# RPi-Proto-HAT_v10.net
KiCad netlist of a schematic drawn in EAGLE
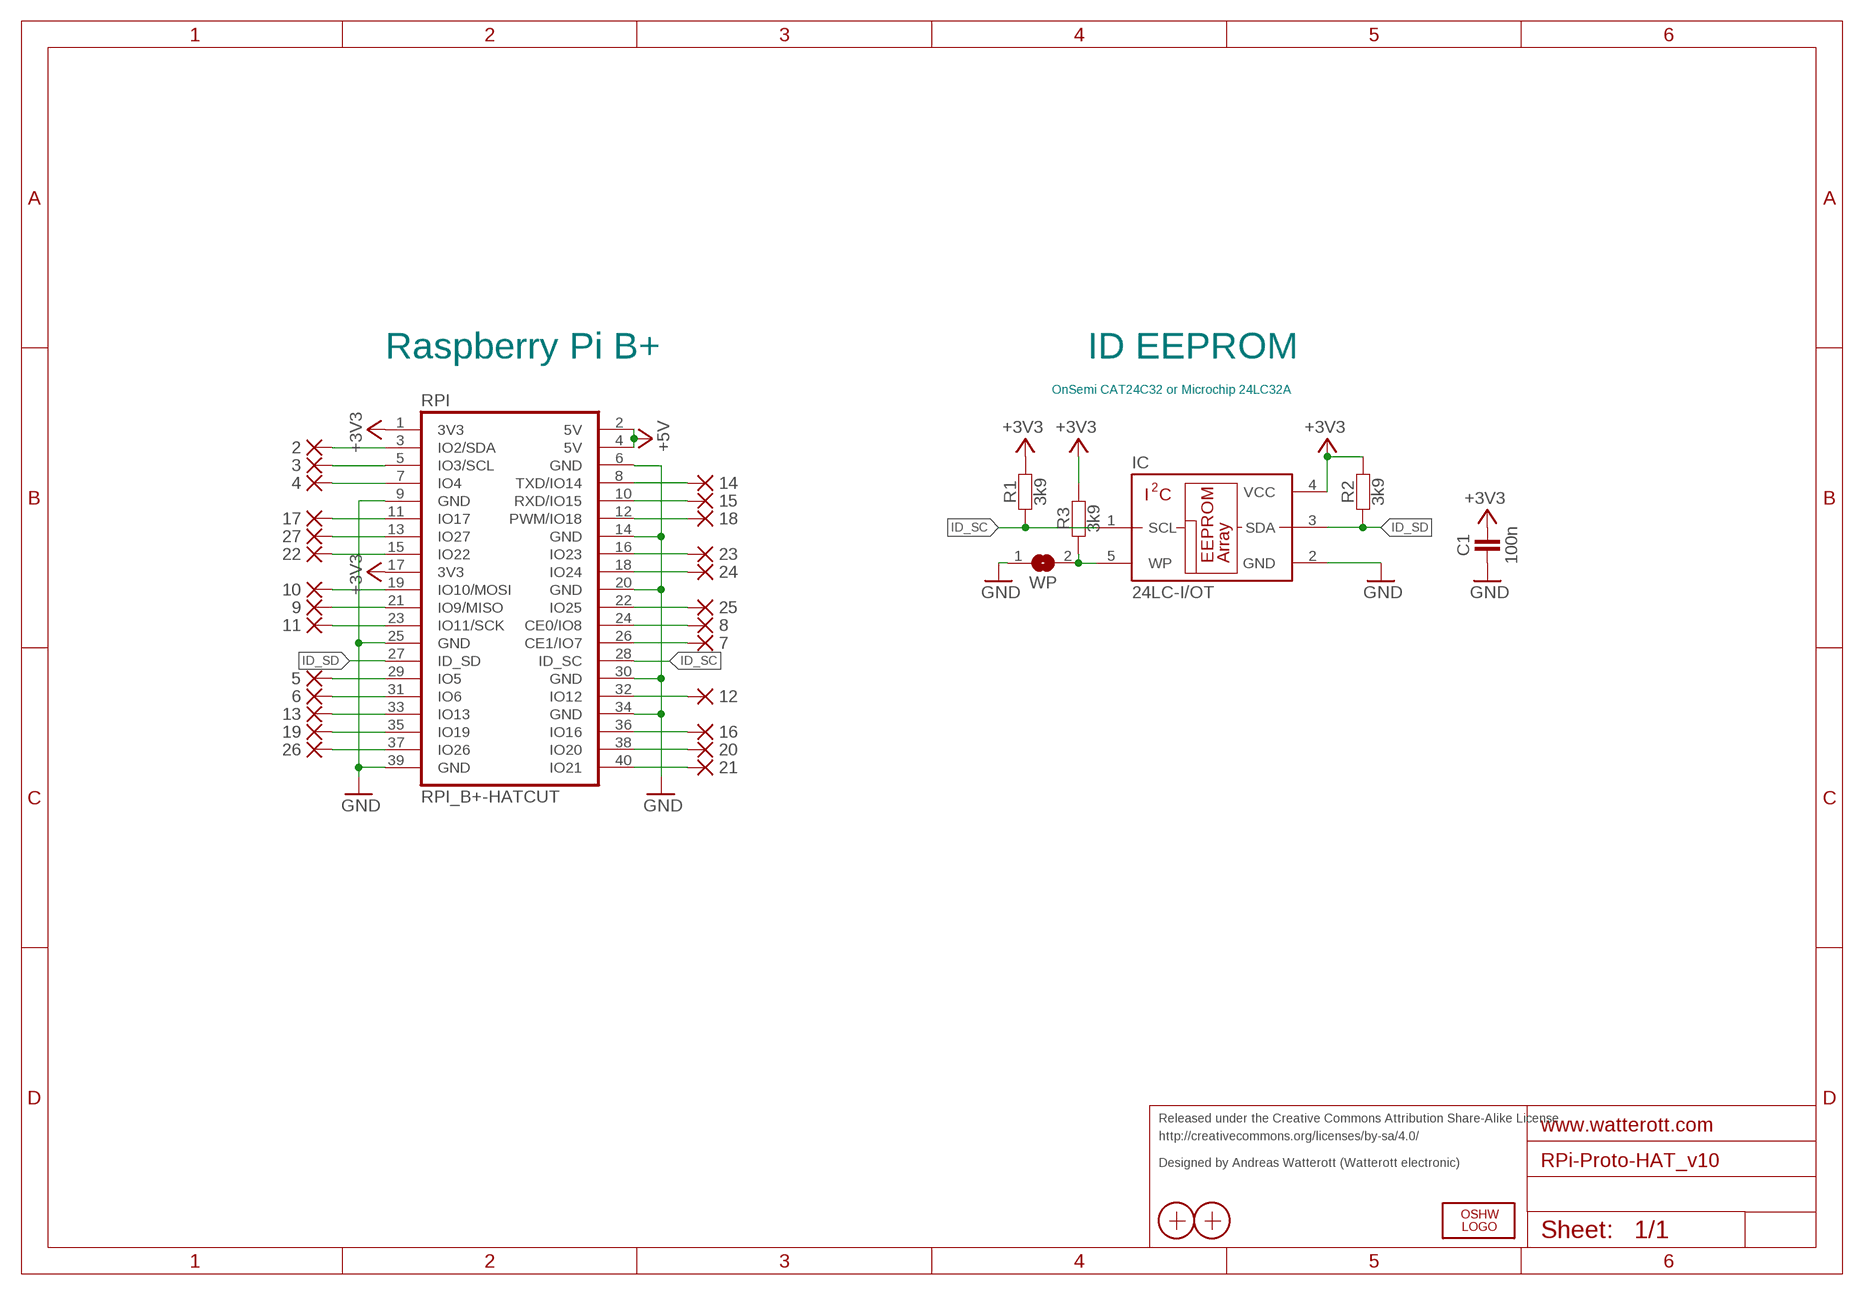
[diagram p0: schematic, sheet 1]

(export (version "E")
  (design (tool "Eeschema 10.0.6"))
  (components
    (comp (ref "2")
      (value "PAD-1-1.6")
      (footprint "eagle-import:PAD-1-1.6")
      (libsource (lib "eagle-import") (part "PAD-1-1.6"))
    )
    (comp (ref "3")
      (value "PAD-1-1.6")
      (footprint "eagle-import:PAD-1-1.6")
      (libsource (lib "eagle-import") (part "PAD-1-1.6"))
    )
    (comp (ref "4")
      (value "PAD-1-1.6")
      (footprint "eagle-import:PAD-1-1.6")
      (libsource (lib "eagle-import") (part "PAD-1-1.6"))
    )
    (comp (ref "5")
      (value "PAD-1-1.6")
      (footprint "eagle-import:PAD-1-1.6")
      (libsource (lib "eagle-import") (part "PAD-1-1.6"))
    )
    (comp (ref "6")
      (value "PAD-1-1.6")
      (footprint "eagle-import:PAD-1-1.6")
      (libsource (lib "eagle-import") (part "PAD-1-1.6"))
    )
    (comp (ref "7")
      (value "PAD-1-1.6")
      (footprint "eagle-import:PAD-1-1.6")
      (libsource (lib "eagle-import") (part "PAD-1-1.6"))
    )
    (comp (ref "8")
      (value "PAD-1-1.6")
      (footprint "eagle-import:PAD-1-1.6")
      (libsource (lib "eagle-import") (part "PAD-1-1.6"))
    )
    (comp (ref "9")
      (value "PAD-1-1.6")
      (footprint "eagle-import:PAD-1-1.6")
      (libsource (lib "eagle-import") (part "PAD-1-1.6"))
    )
    (comp (ref "10")
      (value "PAD-1-1.6")
      (footprint "eagle-import:PAD-1-1.6")
      (libsource (lib "eagle-import") (part "PAD-1-1.6"))
    )
    (comp (ref "11")
      (value "PAD-1-1.6")
      (footprint "eagle-import:PAD-1-1.6")
      (libsource (lib "eagle-import") (part "PAD-1-1.6"))
    )
    (comp (ref "12")
      (value "PAD-1-1.6")
      (footprint "eagle-import:PAD-1-1.6")
      (libsource (lib "eagle-import") (part "PAD-1-1.6"))
    )
    (comp (ref "13")
      (value "PAD-1-1.6")
      (footprint "eagle-import:PAD-1-1.6")
      (libsource (lib "eagle-import") (part "PAD-1-1.6"))
    )
    (comp (ref "14")
      (value "PAD-1-1.6")
      (footprint "eagle-import:PAD-1-1.6")
      (libsource (lib "eagle-import") (part "PAD-1-1.6"))
    )
    (comp (ref "15")
      (value "PAD-1-1.6")
      (footprint "eagle-import:PAD-1-1.6")
      (libsource (lib "eagle-import") (part "PAD-1-1.6"))
    )
    (comp (ref "16")
      (value "PAD-1-1.6")
      (footprint "eagle-import:PAD-1-1.6")
      (libsource (lib "eagle-import") (part "PAD-1-1.6"))
    )
    (comp (ref "17")
      (value "PAD-1-1.6")
      (footprint "eagle-import:PAD-1-1.6")
      (libsource (lib "eagle-import") (part "PAD-1-1.6"))
    )
    (comp (ref "18")
      (value "PAD-1-1.6")
      (footprint "eagle-import:PAD-1-1.6")
      (libsource (lib "eagle-import") (part "PAD-1-1.6"))
    )
    (comp (ref "19")
      (value "PAD-1-1.6")
      (footprint "eagle-import:PAD-1-1.6")
      (libsource (lib "eagle-import") (part "PAD-1-1.6"))
    )
    (comp (ref "20")
      (value "PAD-1-1.6")
      (footprint "eagle-import:PAD-1-1.6")
      (libsource (lib "eagle-import") (part "PAD-1-1.6"))
    )
    (comp (ref "21")
      (value "PAD-1-1.6")
      (footprint "eagle-import:PAD-1-1.6")
      (libsource (lib "eagle-import") (part "PAD-1-1.6"))
    )
    (comp (ref "22")
      (value "PAD-1-1.6")
      (footprint "eagle-import:PAD-1-1.6")
      (libsource (lib "eagle-import") (part "PAD-1-1.6"))
    )
    (comp (ref "23")
      (value "PAD-1-1.6")
      (footprint "eagle-import:PAD-1-1.6")
      (libsource (lib "eagle-import") (part "PAD-1-1.6"))
    )
    (comp (ref "24")
      (value "PAD-1-1.6")
      (footprint "eagle-import:PAD-1-1.6")
      (libsource (lib "eagle-import") (part "PAD-1-1.6"))
    )
    (comp (ref "25")
      (value "PAD-1-1.6")
      (footprint "eagle-import:PAD-1-1.6")
      (libsource (lib "eagle-import") (part "PAD-1-1.6"))
    )
    (comp (ref "26")
      (value "PAD-1-1.6")
      (footprint "eagle-import:PAD-1-1.6")
      (libsource (lib "eagle-import") (part "PAD-1-1.6"))
    )
    (comp (ref "27")
      (value "PAD-1-1.6")
      (footprint "eagle-import:PAD-1-1.6")
      (libsource (lib "eagle-import") (part "PAD-1-1.6"))
    )
    (comp (ref "C1")
      (value "100n")
      (footprint "eagle-import:R0603")
      (libsource (lib "eagle-import") (part "CAPACITOR-C0603"))
    )
    (comp (ref "IC")
      (value "24LC-I/OT")
      (footprint "eagle-import:SOT23-5")
      (libsource (lib "eagle-import") (part "24LC-I/OT"))
    )
    (comp (ref "LOGO2")
      (value "OSHW_LOGOX0070")
      (footprint "eagle-import:OSHW_6X70")
      (libsource (lib "eagle-import") (part "OSHW_LOGOX0070"))
    )
    (comp (ref "R1")
      (value "3k9")
      (footprint "eagle-import:R0603")
      (libsource (lib "eagle-import") (part "RESISTOR-R0603"))
    )
    (comp (ref "R2")
      (value "3k9")
      (footprint "eagle-import:R0603")
      (libsource (lib "eagle-import") (part "RESISTOR-R0603"))
    )
    (comp (ref "R3")
      (value "3k9")
      (footprint "eagle-import:R0603")
      (libsource (lib "eagle-import") (part "RESISTOR-R0603"))
    )
    (comp (ref "RPI")
      (value "RPI_B+-HATCUT")
      (footprint "eagle-import:RPI-B+HAT_CUTOUT")
      (libsource (lib "eagle-import") (part "RPI_B+-HATCUT"))
    )
    (comp (ref "WP")
      (value "JUMPER2-NOCREAM")
      (footprint "eagle-import:JUMPER2_NC")
      (libsource (lib "eagle-import") (part "JUMPER2-NOCREAM"))
    )
    (comp (ref "X1")
      (value "PASSER-07")
      (footprint "eagle-import:PASSER_07MM")
      (libsource (lib "eagle-import") (part "PASSER-07"))
    )
    (comp (ref "X2")
      (value "PASSER-07")
      (footprint "eagle-import:PASSER_07MM")
      (libsource (lib "eagle-import") (part "PASSER-07"))
    )
  )
  (nets
    (net (code "1") (name "+3V3") (class "Default")
      (node (ref "C1") (pin "2") (pinfunction "2_2") (pintype "passive"))
      (node (ref "IC") (pin "4") (pinfunction "VCC_4") (pintype "power_in"))
      (node (ref "R1") (pin "2") (pinfunction "2_2") (pintype "passive"))
      (node (ref "R2") (pin "2") (pinfunction "2_2") (pintype "passive"))
      (node (ref "R3") (pin "2") (pinfunction "2_2") (pintype "passive"))
      (node (ref "RPI") (pin "1") (pinfunction "3V3_1") (pintype "passive"))
      (node (ref "RPI") (pin "17") (pinfunction "3V3_17") (pintype "passive"))
    )
    (net (code "2") (name "+5V") (class "Default")
      (node (ref "RPI") (pin "2") (pinfunction "5V_2") (pintype "passive"))
      (node (ref "RPI") (pin "4") (pinfunction "5V_4") (pintype "passive"))
    )
    (net (code "3") (name "GND") (class "Default")
      (node (ref "C1") (pin "1") (pinfunction "1_1") (pintype "passive"))
      (node (ref "IC") (pin "2") (pinfunction "GND_2") (pintype "power_in"))
      (node (ref "RPI") (pin "14") (pinfunction "GND_14") (pintype "passive"))
      (node (ref "RPI") (pin "20") (pinfunction "GND_20") (pintype "passive"))
      (node (ref "RPI") (pin "25") (pinfunction "GND_25") (pintype "passive"))
      (node (ref "RPI") (pin "30") (pinfunction "GND_30") (pintype "bidirectional"))
      (node (ref "RPI") (pin "34") (pinfunction "GND_34") (pintype "bidirectional"))
      (node (ref "RPI") (pin "39") (pinfunction "GND_39") (pintype "bidirectional"))
      (node (ref "RPI") (pin "6") (pinfunction "GND_6") (pintype "passive"))
      (node (ref "RPI") (pin "9") (pinfunction "GND_9") (pintype "passive"))
      (node (ref "WP") (pin "1") (pinfunction "1_1") (pintype "passive"))
    )
    (net (code "4") (name "ID_SC") (class "Default")
      (node (ref "IC") (pin "1") (pinfunction "SCL_1") (pintype "bidirectional"))
      (node (ref "R1") (pin "1") (pinfunction "1_1") (pintype "passive"))
      (node (ref "RPI") (pin "28") (pinfunction "ID_SC_28") (pintype "bidirectional"))
    )
    (net (code "5") (name "ID_SD") (class "Default")
      (node (ref "IC") (pin "3") (pinfunction "SDA_3") (pintype "bidirectional"))
      (node (ref "R2") (pin "1") (pinfunction "1_1") (pintype "passive"))
      (node (ref "RPI") (pin "27") (pinfunction "ID_SD_27") (pintype "bidirectional"))
    )
    (net (code "6") (name "Net-(2-P)") (class "Default")
      (node (ref "2") (pin "1") (pinfunction "P_1") (pintype "passive"))
      (node (ref "RPI") (pin "3") (pinfunction "IO2/SDA_3") (pintype "passive"))
    )
    (net (code "7") (name "Net-(3-P)") (class "Default")
      (node (ref "3") (pin "1") (pinfunction "P_1") (pintype "passive"))
      (node (ref "RPI") (pin "5") (pinfunction "IO3/SCL_5") (pintype "passive"))
    )
    (net (code "8") (name "Net-(4-P)") (class "Default")
      (node (ref "4") (pin "1") (pinfunction "P_1") (pintype "passive"))
      (node (ref "RPI") (pin "7") (pinfunction "IO4_7") (pintype "passive"))
    )
    (net (code "9") (name "Net-(5-P)") (class "Default")
      (node (ref "5") (pin "1") (pinfunction "P_1") (pintype "passive"))
      (node (ref "RPI") (pin "29") (pinfunction "IO5_29") (pintype "bidirectional"))
    )
    (net (code "10") (name "Net-(6-P)") (class "Default")
      (node (ref "6") (pin "1") (pinfunction "P_1") (pintype "passive"))
      (node (ref "RPI") (pin "31") (pinfunction "IO6_31") (pintype "bidirectional"))
    )
    (net (code "11") (name "Net-(7-P)") (class "Default")
      (node (ref "7") (pin "1") (pinfunction "P_1") (pintype "passive"))
      (node (ref "RPI") (pin "26") (pinfunction "CE1/IO7_26") (pintype "passive"))
    )
    (net (code "12") (name "Net-(8-P)") (class "Default")
      (node (ref "8") (pin "1") (pinfunction "P_1") (pintype "passive"))
      (node (ref "RPI") (pin "24") (pinfunction "CE0/IO8_24") (pintype "passive"))
    )
    (net (code "13") (name "Net-(9-P)") (class "Default")
      (node (ref "9") (pin "1") (pinfunction "P_1") (pintype "passive"))
      (node (ref "RPI") (pin "21") (pinfunction "IO9/MISO_21") (pintype "passive"))
    )
    (net (code "14") (name "Net-(10-P)") (class "Default")
      (node (ref "10") (pin "1") (pinfunction "P_1") (pintype "passive"))
      (node (ref "RPI") (pin "19") (pinfunction "IO10/MOSI_19") (pintype "passive"))
    )
    (net (code "15") (name "Net-(11-P)") (class "Default")
      (node (ref "11") (pin "1") (pinfunction "P_1") (pintype "passive"))
      (node (ref "RPI") (pin "23") (pinfunction "IO11/SCK_23") (pintype "passive"))
    )
    (net (code "16") (name "Net-(12-P)") (class "Default")
      (node (ref "12") (pin "1") (pinfunction "P_1") (pintype "passive"))
      (node (ref "RPI") (pin "32") (pinfunction "IO12_32") (pintype "bidirectional"))
    )
    (net (code "17") (name "Net-(13-P)") (class "Default")
      (node (ref "13") (pin "1") (pinfunction "P_1") (pintype "passive"))
      (node (ref "RPI") (pin "33") (pinfunction "IO13_33") (pintype "bidirectional"))
    )
    (net (code "18") (name "Net-(14-P)") (class "Default")
      (node (ref "14") (pin "1") (pinfunction "P_1") (pintype "passive"))
      (node (ref "RPI") (pin "8") (pinfunction "TXD/IO14_8") (pintype "passive"))
    )
    (net (code "19") (name "Net-(15-P)") (class "Default")
      (node (ref "15") (pin "1") (pinfunction "P_1") (pintype "passive"))
      (node (ref "RPI") (pin "10") (pinfunction "RXD/IO15_10") (pintype "passive"))
    )
    (net (code "20") (name "Net-(16-P)") (class "Default")
      (node (ref "16") (pin "1") (pinfunction "P_1") (pintype "passive"))
      (node (ref "RPI") (pin "36") (pinfunction "IO16_36") (pintype "bidirectional"))
    )
    (net (code "21") (name "Net-(17-P)") (class "Default")
      (node (ref "17") (pin "1") (pinfunction "P_1") (pintype "passive"))
      (node (ref "RPI") (pin "11") (pinfunction "IO17_11") (pintype "passive"))
    )
    (net (code "22") (name "Net-(18-P)") (class "Default")
      (node (ref "18") (pin "1") (pinfunction "P_1") (pintype "passive"))
      (node (ref "RPI") (pin "12") (pinfunction "PWM/IO18_12") (pintype "passive"))
    )
    (net (code "23") (name "Net-(19-P)") (class "Default")
      (node (ref "19") (pin "1") (pinfunction "P_1") (pintype "passive"))
      (node (ref "RPI") (pin "35") (pinfunction "IO19_35") (pintype "bidirectional"))
    )
    (net (code "24") (name "Net-(20-P)") (class "Default")
      (node (ref "20") (pin "1") (pinfunction "P_1") (pintype "passive"))
      (node (ref "RPI") (pin "38") (pinfunction "IO20_38") (pintype "bidirectional"))
    )
    (net (code "25") (name "Net-(21-P)") (class "Default")
      (node (ref "21") (pin "1") (pinfunction "P_1") (pintype "passive"))
      (node (ref "RPI") (pin "40") (pinfunction "IO21_40") (pintype "bidirectional"))
    )
    (net (code "26") (name "Net-(22-P)") (class "Default")
      (node (ref "22") (pin "1") (pinfunction "P_1") (pintype "passive"))
      (node (ref "RPI") (pin "15") (pinfunction "IO22_15") (pintype "passive"))
    )
    (net (code "27") (name "Net-(23-P)") (class "Default")
      (node (ref "23") (pin "1") (pinfunction "P_1") (pintype "passive"))
      (node (ref "RPI") (pin "16") (pinfunction "IO23_16") (pintype "passive"))
    )
    (net (code "28") (name "Net-(24-P)") (class "Default")
      (node (ref "24") (pin "1") (pinfunction "P_1") (pintype "passive"))
      (node (ref "RPI") (pin "18") (pinfunction "IO24_18") (pintype "passive"))
    )
    (net (code "29") (name "Net-(25-P)") (class "Default")
      (node (ref "25") (pin "1") (pinfunction "P_1") (pintype "passive"))
      (node (ref "RPI") (pin "22") (pinfunction "IO25_22") (pintype "passive"))
    )
    (net (code "30") (name "Net-(26-P)") (class "Default")
      (node (ref "26") (pin "1") (pinfunction "P_1") (pintype "passive"))
      (node (ref "RPI") (pin "37") (pinfunction "IO26_37") (pintype "bidirectional"))
    )
    (net (code "31") (name "Net-(27-P)") (class "Default")
      (node (ref "27") (pin "1") (pinfunction "P_1") (pintype "passive"))
      (node (ref "RPI") (pin "13") (pinfunction "IO27_13") (pintype "passive"))
    )
    (net (code "32") (name "Net-(IC-WP)") (class "Default")
      (node (ref "IC") (pin "5") (pinfunction "WP_5") (pintype "bidirectional"))
      (node (ref "R3") (pin "1") (pinfunction "1_1") (pintype "passive"))
      (node (ref "WP") (pin "2") (pinfunction "2_2") (pintype "passive"))
    )
  )
)
